# etapa3_energia.net
KiCad netlist of a schematic drawn in Altium Designer
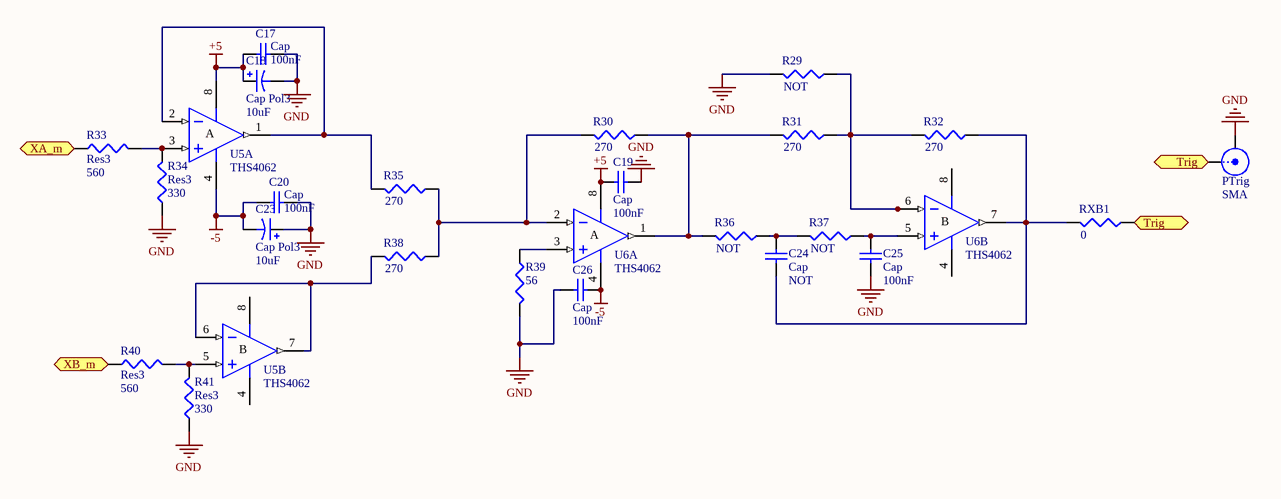
[diagram p0: etapa3_energia.SchDoc]

(export (version "E")
  (design (tool "Eeschema 10.0.6"))
  (components
    (comp (ref "C17")
      (value "Cap")
      (footprint "6-0805_N")
      (description "Capacitor")
      (fields (field (name "ALTIUM_VALUE") "100nF") (field (name "PUBLISHER") "Altium Limited"))
      (libsource (lib "Miscellaneous Devices") (part "Cap"))
    )
    (comp (ref "C18")
      (value "Cap Pol3")
      (footprint "6-0805_N")
      (description "Polarized Capacitor (Surface Mount)")
      (fields (field (name "ALTIUM_VALUE") "10uF") (field (name "PUBLISHER") "Altium Limited"))
      (libsource (lib "Miscellaneous Devices") (part "Cap Pol3"))
    )
    (comp (ref "C19")
      (value "Cap")
      (footprint "1608[0603]")
      (description "Capacitor")
      (fields (field (name "ALTIUM_VALUE") "100nF") (field (name "PUBLISHER") "Altium Limited"))
      (libsource (lib "Miscellaneous Devices") (part "Cap"))
    )
    (comp (ref "C20")
      (value "Cap")
      (footprint "6-0805_N")
      (description "Capacitor")
      (fields (field (name "ALTIUM_VALUE") "100nF") (field (name "PUBLISHER") "Altium Limited"))
      (libsource (lib "Miscellaneous Devices") (part "Cap"))
    )
    (comp (ref "C23")
      (value "Cap Pol3")
      (footprint "6-0805_N")
      (description "Polarized Capacitor (Surface Mount)")
      (fields (field (name "ALTIUM_VALUE") "10uF") (field (name "PUBLISHER") "Altium Limited"))
      (libsource (lib "Miscellaneous Devices") (part "Cap Pol3"))
    )
    (comp (ref "C24")
      (value "Cap")
      (footprint "1608[0603]")
      (description "Capacitor")
      (fields (field (name "ALTIUM_VALUE") "NOT") (field (name "PUBLISHER") "Altium Limited"))
      (libsource (lib "Miscellaneous Devices") (part "Cap"))
    )
    (comp (ref "C25")
      (value "Cap")
      (footprint "1608[0603]")
      (description "Capacitor")
      (fields (field (name "ALTIUM_VALUE") "100nF") (field (name "PUBLISHER") "Altium Limited"))
      (libsource (lib "Miscellaneous Devices") (part "Cap"))
    )
    (comp (ref "C26")
      (value "Cap")
      (footprint "1608[0603]")
      (description "Capacitor")
      (fields (field (name "ALTIUM_VALUE") "100nF") (field (name "PUBLISHER") "Altium Limited"))
      (libsource (lib "Miscellaneous Devices") (part "Cap"))
    )
    (comp (ref "PTrig")
      (value "SMA")
      (footprint "SMB_V-RJ45")
      (description "SMB Straight Connector")
      (fields (field (name "PUBLISHER") "Altium Limited"))
      (libsource (lib "Miscellaneous Connectors") (part "SMB"))
    )
    (comp (ref "R29")
      (value "NOT")
      (footprint "J1-0603")
      (description "Resistor")
      (fields (field (name "Comment") "Res3") (field (name "PUBLISHER") "Altium Limited"))
      (libsource (lib "Miscellaneous Devices") (part "Res3"))
    )
    (comp (ref "R30")
      (value "270")
      (footprint "J1-0603")
      (description "Resistor")
      (fields (field (name "Comment") "Res3") (field (name "PUBLISHER") "Altium Limited"))
      (libsource (lib "Miscellaneous Devices") (part "Res3"))
    )
    (comp (ref "R31")
      (value "270")
      (footprint "J1-0603")
      (description "Resistor")
      (fields (field (name "Comment") "Res3") (field (name "PUBLISHER") "Altium Limited"))
      (libsource (lib "Miscellaneous Devices") (part "Res3"))
    )
    (comp (ref "R32")
      (value "270")
      (footprint "J1-0603")
      (description "Resistor")
      (fields (field (name "Comment") "Res3") (field (name "PUBLISHER") "Altium Limited"))
      (libsource (lib "Miscellaneous Devices") (part "Res3"))
    )
    (comp (ref "R33")
      (value "Res3")
      (footprint "J1-0603")
      (description "Resistor")
      (fields (field (name "ALTIUM_VALUE") "560") (field (name "PUBLISHER") "Altium Limited"))
      (libsource (lib "Miscellaneous Devices") (part "Res3"))
    )
    (comp (ref "R34")
      (value "Res3")
      (footprint "J1-0603")
      (description "Resistor")
      (fields (field (name "ALTIUM_VALUE") "330") (field (name "PUBLISHER") "Altium Limited"))
      (libsource (lib "Miscellaneous Devices") (part "Res3"))
    )
    (comp (ref "R35")
      (value "270")
      (footprint "J1-0603")
      (description "Resistor")
      (fields (field (name "Comment") "Res3") (field (name "PUBLISHER") "Altium Limited"))
      (libsource (lib "Miscellaneous Devices") (part "Res3"))
    )
    (comp (ref "R36")
      (value "NOT")
      (footprint "J1-0603")
      (description "Resistor")
      (fields (field (name "Comment") "Res3") (field (name "PUBLISHER") "Altium Limited"))
      (libsource (lib "Miscellaneous Devices") (part "Res3"))
    )
    (comp (ref "R37")
      (value "NOT")
      (footprint "J1-0603")
      (description "Resistor")
      (fields (field (name "Comment") "Res3") (field (name "PUBLISHER") "Altium Limited"))
      (libsource (lib "Miscellaneous Devices") (part "Res3"))
    )
    (comp (ref "R38")
      (value "270")
      (footprint "J1-0603")
      (description "Resistor")
      (fields (field (name "Comment") "Res3") (field (name "PUBLISHER") "Altium Limited"))
      (libsource (lib "Miscellaneous Devices") (part "Res3"))
    )
    (comp (ref "R39")
      (value "56")
      (footprint "J1-0603")
      (description "Resistor")
      (fields (field (name "Comment") "Res3") (field (name "PUBLISHER") "Altium Limited"))
      (libsource (lib "Miscellaneous Devices") (part "Res3"))
    )
    (comp (ref "R40")
      (value "Res3")
      (footprint "J1-0603")
      (description "Resistor")
      (fields (field (name "ALTIUM_VALUE") "560") (field (name "PUBLISHER") "Altium Limited"))
      (libsource (lib "Miscellaneous Devices") (part "Res3"))
    )
    (comp (ref "R41")
      (value "Res3")
      (footprint "J1-0603")
      (description "Resistor")
      (fields (field (name "ALTIUM_VALUE") "330") (field (name "PUBLISHER") "Altium Limited"))
      (libsource (lib "Miscellaneous Devices") (part "Res3"))
    )
    (comp (ref "RXB1")
      (value "0")
      (footprint "J1-0603")
      (description "Resistor")
      (fields (field (name "Comment") "Res3") (field (name "PUBLISHER") "Altium Limited"))
      (libsource (lib "Miscellaneous Devices") (part "Res3"))
    )
    (comp (ref "U5")
      (value "THS4062")
      (footprint "SO-8_M")
      (description "Dual 600MHz, 50mW Current Feedback Amplifier")
      (fields (field (name "PUBLISHER") "Altium Limited"))
      (libsource (lib "AD Operational Amplifier") (part "AD8002AR"))
    )
    (comp (ref "U6")
      (value "THS4062")
      (footprint "SO-8_M")
      (description "Dual 600MHz, 50mW Current Feedback Amplifier")
      (fields (field (name "PUBLISHER") "Altium Limited"))
      (libsource (lib "AD Operational Amplifier") (part "AD8002AR"))
    )
  )
  (nets
    (net (code "1") (name "+5") (class "Default")
      (node (ref "C17") (pin "2") (pinfunction "2_2") (pintype "passive"))
      (node (ref "C18") (pin "1") (pinfunction "1_1") (pintype "passive"))
      (node (ref "C19") (pin "1") (pinfunction "1_1") (pintype "passive"))
      (node (ref "U5") (pin "8") (pinfunction "V+_8") (pintype "power_in"))
      (node (ref "U6") (pin "8") (pinfunction "V+_8") (pintype "power_in"))
    )
    (net (code "2") (name "-5") (class "Default")
      (node (ref "C20") (pin "2") (pinfunction "2_2") (pintype "passive"))
      (node (ref "C23") (pin "2") (pinfunction "2_2") (pintype "passive"))
      (node (ref "C26") (pin "2") (pinfunction "2_2") (pintype "passive"))
      (node (ref "U5") (pin "4") (pinfunction "V-_4") (pintype "power_in"))
      (node (ref "U6") (pin "4") (pinfunction "V-_4") (pintype "power_in"))
    )
    (net (code "3") (name "/Trig") (class "Default")
      (node (ref "PTrig") (pin "1") (pinfunction "X_1") (pintype "passive"))
      (node (ref "RXB1") (pin "1") (pinfunction "1_1") (pintype "passive"))
    )
    (net (code "4") (name "/XA_m") (class "Default")
      (node (ref "R33") (pin "1") (pinfunction "1_1") (pintype "passive"))
    )
    (net (code "5") (name "/XB_m") (class "Default")
      (node (ref "R40") (pin "1") (pinfunction "1_1") (pintype "passive"))
    )
    (net (code "6") (name "GND") (class "Default")
      (node (ref "C17") (pin "1") (pinfunction "1_1") (pintype "passive"))
      (node (ref "C18") (pin "2") (pinfunction "2_2") (pintype "passive"))
      (node (ref "C19") (pin "2") (pinfunction "2_2") (pintype "passive"))
      (node (ref "C20") (pin "1") (pinfunction "1_1") (pintype "passive"))
      (node (ref "C23") (pin "1") (pinfunction "1_1") (pintype "passive"))
      (node (ref "C25") (pin "2") (pinfunction "2_2") (pintype "passive"))
      (node (ref "C26") (pin "1") (pinfunction "1_1") (pintype "passive"))
      (node (ref "PTrig") (pin "2") (pinfunction "Y_2") (pintype "passive"))
      (node (ref "R29") (pin "2") (pinfunction "2_2") (pintype "passive"))
      (node (ref "R34") (pin "1") (pinfunction "1_1") (pintype "passive"))
      (node (ref "R39") (pin "2") (pinfunction "2_2") (pintype "passive"))
      (node (ref "R41") (pin "1") (pinfunction "1_1") (pintype "passive"))
    )
    (net (code "7") (name "Net-(C24-Pad1)") (class "Default")
      (node (ref "C24") (pin "1") (pinfunction "1_1") (pintype "passive"))
      (node (ref "R36") (pin "1") (pinfunction "1_1") (pintype "passive"))
      (node (ref "R37") (pin "2") (pinfunction "2_2") (pintype "passive"))
    )
    (net (code "8") (name "Net-(U5A-IN+)") (class "Default")
      (node (ref "R33") (pin "2") (pinfunction "2_2") (pintype "passive"))
      (node (ref "R34") (pin "2") (pinfunction "2_2") (pintype "passive"))
      (node (ref "U5") (pin "3") (pinfunction "IN+_3") (pintype "input"))
    )
    (net (code "9") (name "Net-(U5A-IN-)") (class "Default")
      (node (ref "R35") (pin "2") (pinfunction "2_2") (pintype "passive"))
      (node (ref "U5") (pin "1") (pinfunction "OUT_1") (pintype "output"))
      (node (ref "U5") (pin "2") (pinfunction "IN-_2") (pintype "input"))
    )
    (net (code "10") (name "Net-(U5B-IN+)") (class "Default")
      (node (ref "R40") (pin "2") (pinfunction "2_2") (pintype "passive"))
      (node (ref "R41") (pin "2") (pinfunction "2_2") (pintype "passive"))
      (node (ref "U5") (pin "5") (pinfunction "IN+_5") (pintype "input"))
    )
    (net (code "11") (name "Net-(U5B-IN-)") (class "Default")
      (node (ref "R38") (pin "2") (pinfunction "2_2") (pintype "passive"))
      (node (ref "U5") (pin "6") (pinfunction "IN-_6") (pintype "input"))
      (node (ref "U5") (pin "7") (pinfunction "OUT_7") (pintype "output"))
    )
    (net (code "12") (name "Net-(U6A-IN+)") (class "Default")
      (node (ref "R39") (pin "1") (pinfunction "1_1") (pintype "passive"))
      (node (ref "U6") (pin "3") (pinfunction "IN+_3") (pintype "input"))
    )
    (net (code "13") (name "Net-(U6A-IN-)") (class "Default")
      (node (ref "R30") (pin "2") (pinfunction "2_2") (pintype "passive"))
      (node (ref "R35") (pin "1") (pinfunction "1_1") (pintype "passive"))
      (node (ref "R38") (pin "1") (pinfunction "1_1") (pintype "passive"))
      (node (ref "U6") (pin "2") (pinfunction "IN-_2") (pintype "input"))
    )
    (net (code "14") (name "Net-(U6A-OUT)") (class "Default")
      (node (ref "R30") (pin "1") (pinfunction "1_1") (pintype "passive"))
      (node (ref "R31") (pin "2") (pinfunction "2_2") (pintype "passive"))
      (node (ref "R36") (pin "2") (pinfunction "2_2") (pintype "passive"))
      (node (ref "U6") (pin "1") (pinfunction "OUT_1") (pintype "output"))
    )
    (net (code "15") (name "Net-(U6B-IN+)") (class "Default")
      (node (ref "C25") (pin "1") (pinfunction "1_1") (pintype "passive"))
      (node (ref "R37") (pin "1") (pinfunction "1_1") (pintype "passive"))
      (node (ref "U6") (pin "5") (pinfunction "IN+_5") (pintype "input"))
    )
    (net (code "16") (name "Net-(U6B-IN-)") (class "Default")
      (node (ref "R29") (pin "1") (pinfunction "1_1") (pintype "passive"))
      (node (ref "R31") (pin "1") (pinfunction "1_1") (pintype "passive"))
      (node (ref "R32") (pin "2") (pinfunction "2_2") (pintype "passive"))
      (node (ref "U6") (pin "6") (pinfunction "IN-_6") (pintype "input"))
    )
    (net (code "17") (name "Net-(U6B-OUT)") (class "Default")
      (node (ref "C24") (pin "2") (pinfunction "2_2") (pintype "passive"))
      (node (ref "R32") (pin "1") (pinfunction "1_1") (pintype "passive"))
      (node (ref "RXB1") (pin "2") (pinfunction "2_2") (pintype "passive"))
      (node (ref "U6") (pin "7") (pinfunction "OUT_7") (pintype "output"))
    )
    (net (code "18") (name "unconnected-(U5B-V+-Pad8)") (class "Default")
      (node (ref "U5") (pin "8") (pinfunction "V+_8") (pintype "power_in"))
    )
    (net (code "19") (name "unconnected-(U5B-V--Pad4)") (class "Default")
      (node (ref "U5") (pin "4") (pinfunction "V-_4") (pintype "power_in"))
    )
    (net (code "20") (name "unconnected-(U6B-V+-Pad8)") (class "Default")
      (node (ref "U6") (pin "8") (pinfunction "V+_8") (pintype "power_in"))
    )
    (net (code "21") (name "unconnected-(U6B-V--Pad4)") (class "Default")
      (node (ref "U6") (pin "4") (pinfunction "V-_4") (pintype "power_in"))
    )
  )
)
